# usb_blaster.net
KiCad netlist of a schematic drawn in EAGLE
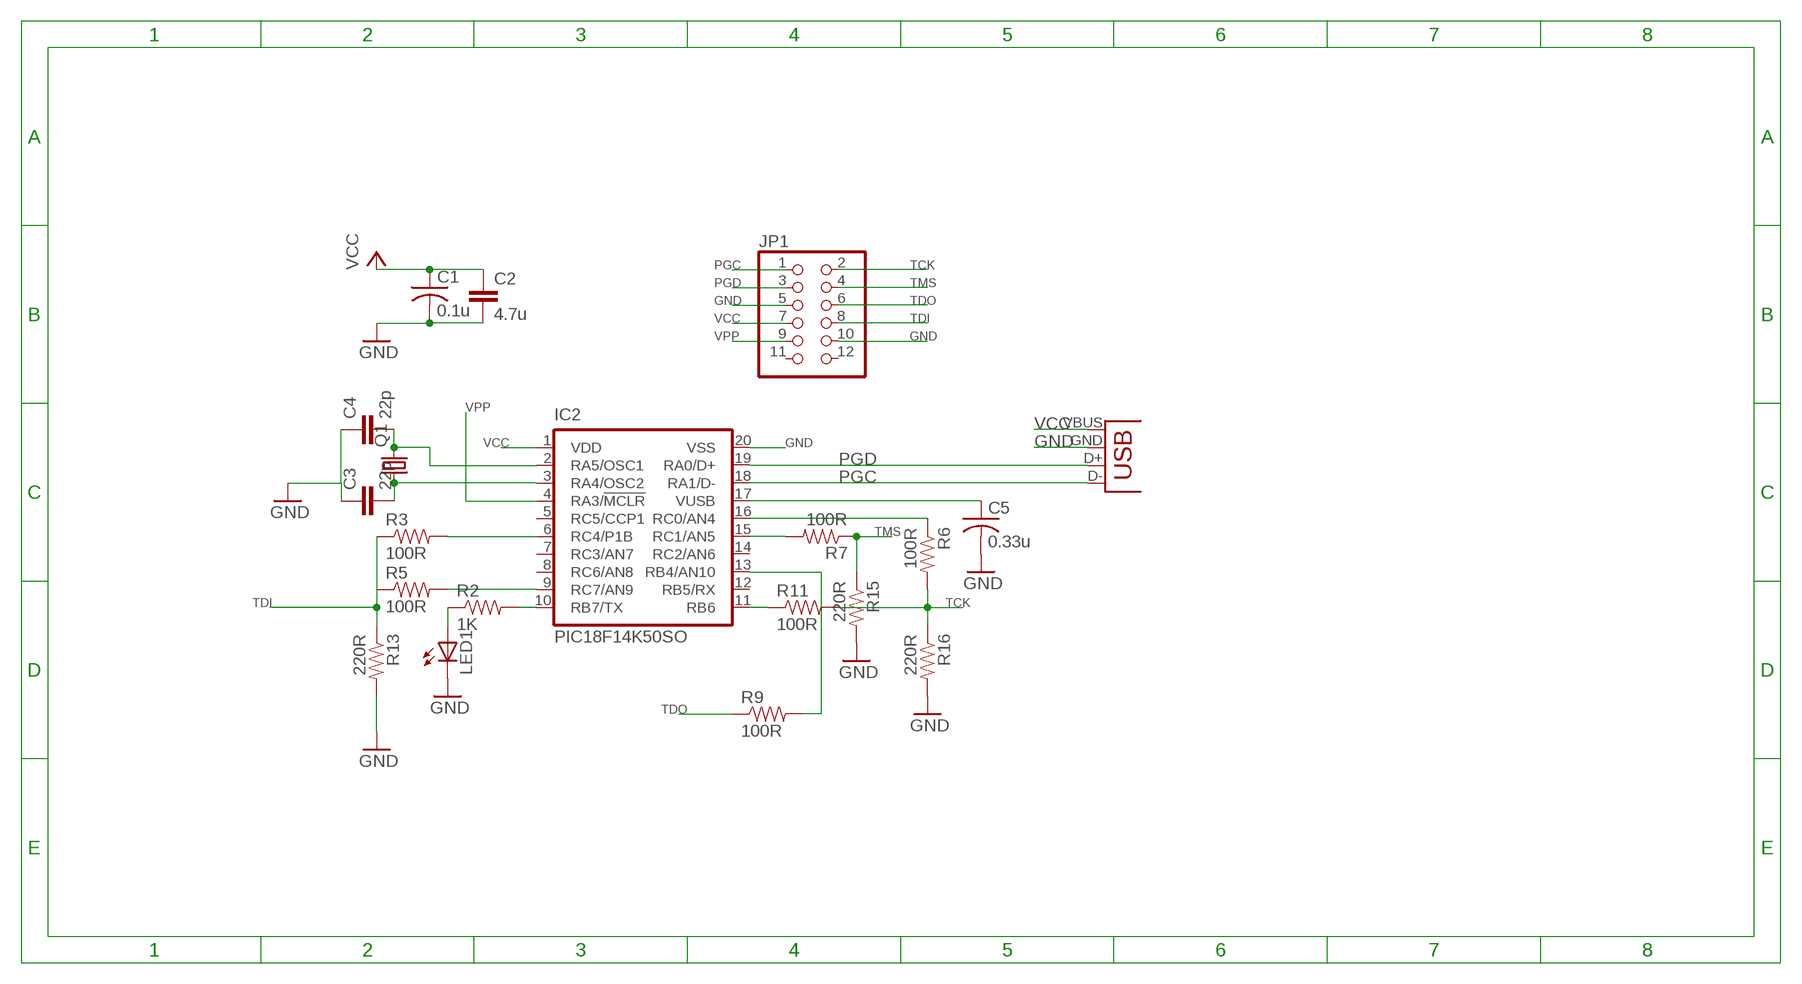
[diagram p0: schematic, sheet 1]

(export (version "E")
  (design (tool "Eeschema 10.0.6"))
  (components
    (comp (ref "C1")
      (value "0.1u")
      (footprint "eagle-import:C0603K")
      (libsource (lib "eagle-import") (part "C-USC0603K"))
    )
    (comp (ref "C2")
      (value "4.7u")
      (footprint "eagle-import:0805")
      (libsource (lib "eagle-import") (part "CAP0805"))
    )
    (comp (ref "C3")
      (value "22p")
      (footprint "eagle-import:0805")
      (libsource (lib "eagle-import") (part "CAP0805"))
    )
    (comp (ref "C4")
      (value "22p")
      (footprint "eagle-import:0805")
      (libsource (lib "eagle-import") (part "CAP0805"))
    )
    (comp (ref "C5")
      (value "0.33u")
      (footprint "eagle-import:C0603K")
      (libsource (lib "eagle-import") (part "C-USC0603K"))
    )
    (comp (ref "IC2")
      (value "PIC18F14K50SO")
      (footprint "eagle-import:SO20")
      (libsource (lib "eagle-import") (part "PIC18F14K50SO"))
    )
    (comp (ref "JP1")
      (value "PINHD-2X6")
      (footprint "eagle-import:2X06")
      (libsource (lib "eagle-import") (part "PINHD-2X6"))
    )
    (comp (ref "LED1")
      (value "LEDCHIP-LED0805")
      (footprint "eagle-import:CHIP-LED0805")
      (libsource (lib "eagle-import") (part "LEDCHIP-LED0805"))
    )
    (comp (ref "Q1")
      (value "CRYSTALHC49UP")
      (footprint "eagle-import:HC49UP")
      (libsource (lib "eagle-import") (part "CRYSTALHC49UP"))
    )
    (comp (ref "R2")
      (value "1K")
      (footprint "eagle-import:0805")
      (libsource (lib "eagle-import") (part "RESISTOR0805-RES"))
    )
    (comp (ref "R3")
      (value "100R")
      (footprint "eagle-import:0805")
      (libsource (lib "eagle-import") (part "RESISTOR0805-RES"))
    )
    (comp (ref "R5")
      (value "100R")
      (footprint "eagle-import:0805")
      (libsource (lib "eagle-import") (part "RESISTOR0805-RES"))
    )
    (comp (ref "R6")
      (value "100R")
      (footprint "eagle-import:0805")
      (libsource (lib "eagle-import") (part "RESISTOR0805-RES"))
    )
    (comp (ref "R7")
      (value "100R")
      (footprint "eagle-import:0805")
      (libsource (lib "eagle-import") (part "RESISTOR0805-RES"))
    )
    (comp (ref "R9")
      (value "100R")
      (footprint "eagle-import:0805")
      (libsource (lib "eagle-import") (part "RESISTOR0805-RES"))
    )
    (comp (ref "R11")
      (value "100R")
      (footprint "eagle-import:0805")
      (libsource (lib "eagle-import") (part "RESISTOR0805-RES"))
    )
    (comp (ref "R13")
      (value "220R")
      (footprint "eagle-import:0805")
      (libsource (lib "eagle-import") (part "RESISTOR0805-RES"))
    )
    (comp (ref "R15")
      (value "220R")
      (footprint "eagle-import:0805")
      (libsource (lib "eagle-import") (part "RESISTOR0805-RES"))
    )
    (comp (ref "R16")
      (value "220R")
      (footprint "eagle-import:0805")
      (libsource (lib "eagle-import") (part "RESISTOR0805-RES"))
    )
    (comp (ref "X2")
      (value "USB-A-H")
      (footprint "eagle-import:USB-A-H")
      (libsource (lib "eagle-import") (part "USB-A-H"))
    )
  )
  (nets
    (net (code "1") (name "/PGC") (class "Default")
      (node (ref "IC2") (pin "18") (pinfunction "RA1/D-_18") (pintype "bidirectional"))
      (node (ref "JP1") (pin "1") (pinfunction "1_1") (pintype "passive"))
      (node (ref "X2") (pin "D-") (pinfunction "D+_D-") (pintype "bidirectional"))
    )
    (net (code "2") (name "/PGD") (class "Default")
      (node (ref "IC2") (pin "19") (pinfunction "RA0/D+_19") (pintype "bidirectional"))
      (node (ref "JP1") (pin "3") (pinfunction "3_3") (pintype "passive"))
      (node (ref "X2") (pin "D+") (pinfunction "D-_D+") (pintype "bidirectional"))
    )
    (net (code "3") (name "/TCK") (class "Default")
      (node (ref "JP1") (pin "2") (pinfunction "2_2") (pintype "passive"))
      (node (ref "R11") (pin "2") (pinfunction "2_2") (pintype "passive"))
      (node (ref "R16") (pin "1") (pinfunction "1_1") (pintype "passive"))
      (node (ref "R6") (pin "2") (pinfunction "2_2") (pintype "passive"))
    )
    (net (code "4") (name "/TDI") (class "Default")
      (node (ref "JP1") (pin "8") (pinfunction "8_8") (pintype "passive"))
      (node (ref "R13") (pin "1") (pinfunction "1_1") (pintype "passive"))
      (node (ref "R3") (pin "1") (pinfunction "1_1") (pintype "passive"))
      (node (ref "R5") (pin "1") (pinfunction "1_1") (pintype "passive"))
    )
    (net (code "5") (name "/TDO") (class "Default")
      (node (ref "JP1") (pin "6") (pinfunction "6_6") (pintype "passive"))
      (node (ref "R9") (pin "1") (pinfunction "1_1") (pintype "passive"))
    )
    (net (code "6") (name "/TMS") (class "Default")
      (node (ref "JP1") (pin "4") (pinfunction "4_4") (pintype "passive"))
      (node (ref "R15") (pin "1") (pinfunction "1_1") (pintype "passive"))
      (node (ref "R7") (pin "1") (pinfunction "1_1") (pintype "passive"))
    )
    (net (code "7") (name "/VPP") (class "Default")
      (node (ref "IC2") (pin "4") (pinfunction "RA3/~{MCLR}_4") (pintype "bidirectional"))
      (node (ref "JP1") (pin "9") (pinfunction "9_9") (pintype "passive"))
    )
    (net (code "8") (name "GND") (class "Default")
      (node (ref "C1") (pin "2") (pinfunction "2_2") (pintype "passive"))
      (node (ref "C2") (pin "2") (pinfunction "2_2") (pintype "passive"))
      (node (ref "C3") (pin "1") (pinfunction "1_1") (pintype "passive"))
      (node (ref "C4") (pin "1") (pinfunction "1_1") (pintype "passive"))
      (node (ref "C5") (pin "2") (pinfunction "2_2") (pintype "passive"))
      (node (ref "IC2") (pin "20") (pinfunction "VSS_20") (pintype "power_in"))
      (node (ref "JP1") (pin "10") (pinfunction "10_10") (pintype "passive"))
      (node (ref "JP1") (pin "5") (pinfunction "5_5") (pintype "passive"))
      (node (ref "LED1") (pin "C") (pinfunction "C_C") (pintype "passive"))
      (node (ref "R13") (pin "2") (pinfunction "2_2") (pintype "passive"))
      (node (ref "R15") (pin "2") (pinfunction "2_2") (pintype "passive"))
      (node (ref "R16") (pin "2") (pinfunction "2_2") (pintype "passive"))
      (node (ref "X2") (pin "GND") (pinfunction "VBUS_GND") (pintype "bidirectional"))
    )
    (net (code "9") (name "Net-(IC2-RA4{slash}OSC2)") (class "Default")
      (node (ref "C3") (pin "2") (pinfunction "2_2") (pintype "passive"))
      (node (ref "IC2") (pin "3") (pinfunction "RA4/OSC2_3") (pintype "bidirectional"))
      (node (ref "Q1") (pin "1") (pinfunction "1_1") (pintype "passive"))
    )
    (net (code "10") (name "Net-(IC2-RA5{slash}OSC1)") (class "Default")
      (node (ref "C4") (pin "2") (pinfunction "2_2") (pintype "passive"))
      (node (ref "IC2") (pin "2") (pinfunction "RA5/OSC1_2") (pintype "bidirectional"))
      (node (ref "Q1") (pin "2") (pinfunction "2_2") (pintype "passive"))
    )
    (net (code "11") (name "Net-(IC2-RB4{slash}AN10)") (class "Default")
      (node (ref "IC2") (pin "13") (pinfunction "RB4/AN10_13") (pintype "bidirectional"))
      (node (ref "R9") (pin "2") (pinfunction "2_2") (pintype "passive"))
    )
    (net (code "12") (name "Net-(IC2-RB6)") (class "Default")
      (node (ref "IC2") (pin "11") (pinfunction "RB6_11") (pintype "bidirectional"))
      (node (ref "R11") (pin "1") (pinfunction "1_1") (pintype "passive"))
    )
    (net (code "13") (name "Net-(IC2-RB7{slash}TX)") (class "Default")
      (node (ref "IC2") (pin "10") (pinfunction "RB7/TX_10") (pintype "bidirectional"))
      (node (ref "R2") (pin "2") (pinfunction "2_2") (pintype "passive"))
    )
    (net (code "14") (name "Net-(IC2-RC0{slash}AN4)") (class "Default")
      (node (ref "IC2") (pin "16") (pinfunction "RC0/AN4_16") (pintype "bidirectional"))
      (node (ref "R6") (pin "1") (pinfunction "1_1") (pintype "passive"))
    )
    (net (code "15") (name "Net-(IC2-RC1{slash}AN5)") (class "Default")
      (node (ref "IC2") (pin "15") (pinfunction "RC1/AN5_15") (pintype "bidirectional"))
      (node (ref "R7") (pin "2") (pinfunction "2_2") (pintype "passive"))
    )
    (net (code "16") (name "Net-(IC2-RC4{slash}P1B)") (class "Default")
      (node (ref "IC2") (pin "6") (pinfunction "RC4/P1B_6") (pintype "bidirectional"))
      (node (ref "R3") (pin "2") (pinfunction "2_2") (pintype "passive"))
    )
    (net (code "17") (name "Net-(IC2-RC7{slash}AN9)") (class "Default")
      (node (ref "IC2") (pin "9") (pinfunction "RC7/AN9_9") (pintype "bidirectional"))
      (node (ref "R5") (pin "2") (pinfunction "2_2") (pintype "passive"))
    )
    (net (code "18") (name "Net-(IC2-VUSB)") (class "Default")
      (node (ref "C5") (pin "1") (pinfunction "1_1") (pintype "passive"))
      (node (ref "IC2") (pin "17") (pinfunction "VUSB_17") (pintype "bidirectional"))
    )
    (net (code "19") (name "Net-(LED1-PadA)") (class "Default")
      (node (ref "LED1") (pin "A") (pinfunction "A_A") (pintype "passive"))
      (node (ref "R2") (pin "1") (pinfunction "1_1") (pintype "passive"))
    )
    (net (code "20") (name "VCC") (class "Default")
      (node (ref "C1") (pin "1") (pinfunction "1_1") (pintype "passive"))
      (node (ref "C2") (pin "1") (pinfunction "1_1") (pintype "passive"))
      (node (ref "IC2") (pin "1") (pinfunction "VDD_1") (pintype "power_in"))
      (node (ref "JP1") (pin "7") (pinfunction "7_7") (pintype "passive"))
      (node (ref "X2") (pin "VBUS") (pinfunction "GND_VBUS") (pintype "bidirectional"))
    )
    (net (code "21") (name "unconnected-(IC2-RB5{slash}RX-Pad12)") (class "Default")
      (node (ref "IC2") (pin "12") (pinfunction "RB5/RX_12") (pintype "bidirectional"))
    )
    (net (code "22") (name "unconnected-(IC2-RC2{slash}AN6-Pad14)") (class "Default")
      (node (ref "IC2") (pin "14") (pinfunction "RC2/AN6_14") (pintype "bidirectional"))
    )
    (net (code "23") (name "unconnected-(IC2-RC3{slash}AN7-Pad7)") (class "Default")
      (node (ref "IC2") (pin "7") (pinfunction "RC3/AN7_7") (pintype "bidirectional"))
    )
    (net (code "24") (name "unconnected-(IC2-RC5{slash}CCP1-Pad5)") (class "Default")
      (node (ref "IC2") (pin "5") (pinfunction "RC5/CCP1_5") (pintype "bidirectional"))
    )
    (net (code "25") (name "unconnected-(IC2-RC6{slash}AN8-Pad8)") (class "Default")
      (node (ref "IC2") (pin "8") (pinfunction "RC6/AN8_8") (pintype "bidirectional"))
    )
    (net (code "26") (name "unconnected-(JP1-Pad11)") (class "Default")
      (node (ref "JP1") (pin "11") (pinfunction "11_11") (pintype "passive"))
    )
    (net (code "27") (name "unconnected-(JP1-Pad12)") (class "Default")
      (node (ref "JP1") (pin "12") (pinfunction "12_12") (pintype "passive"))
    )
  )
)
